# audio_perif.net
KiCad netlist of a schematic drawn in Altium Designer
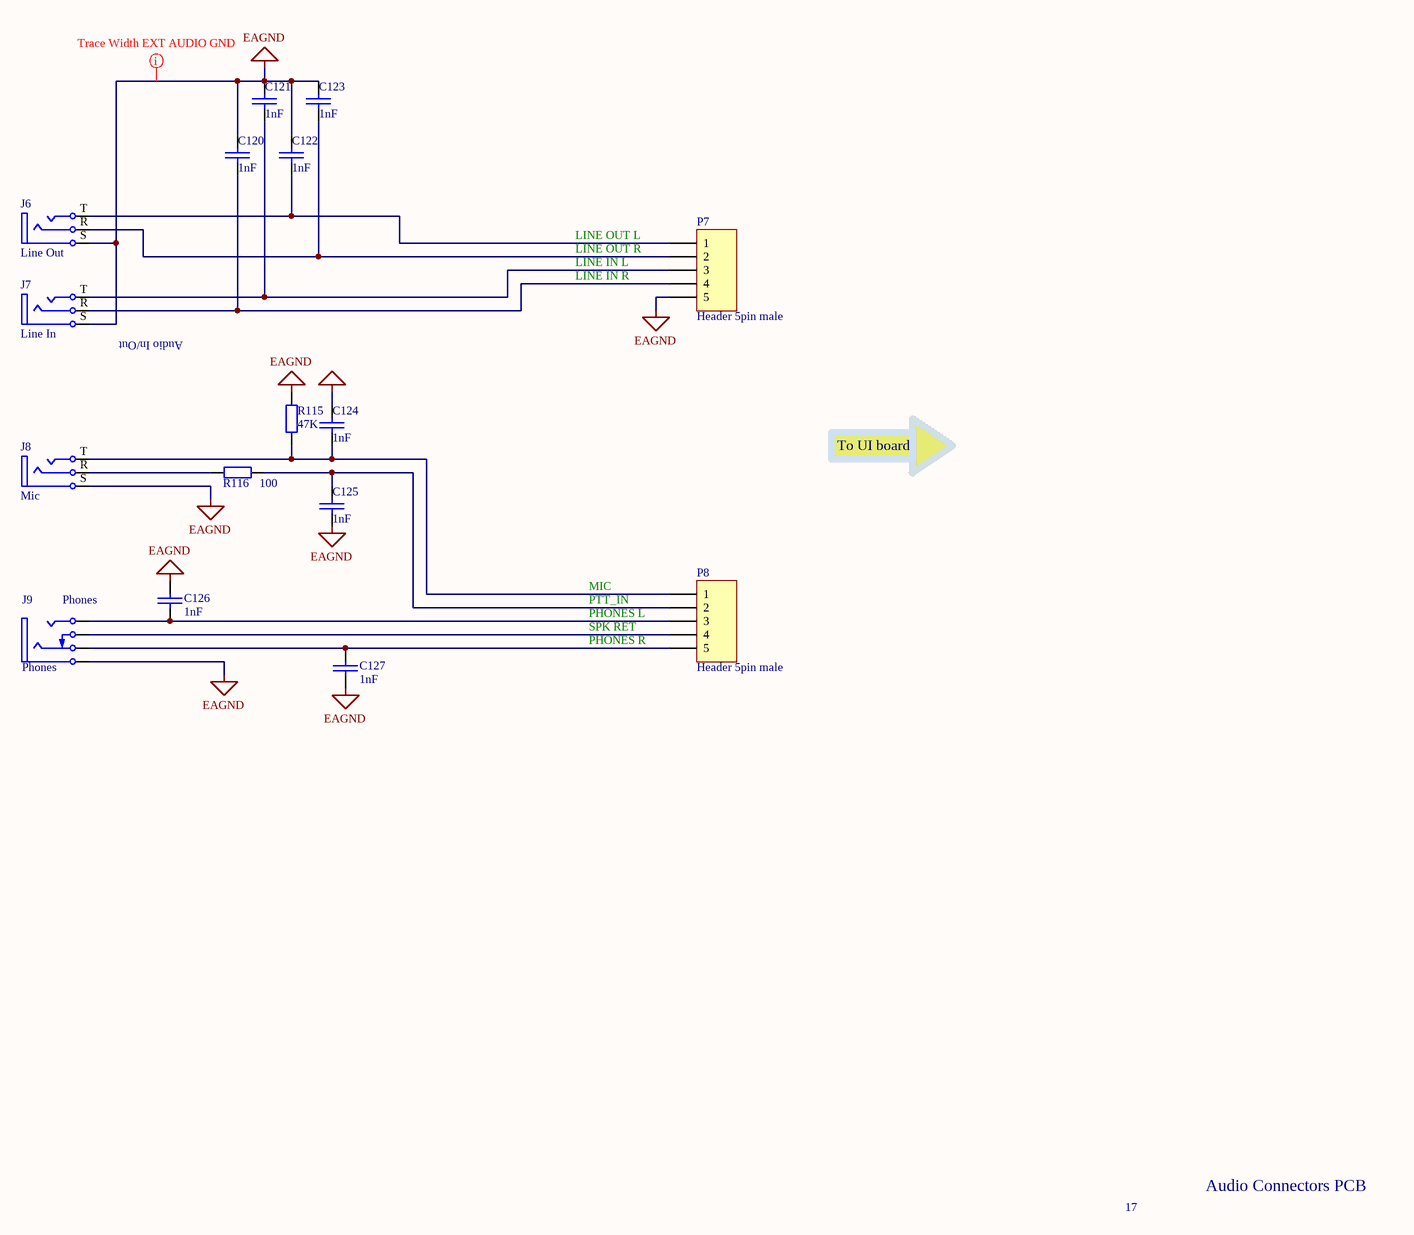
[diagram p0: audio_perif.SchDoc]

(export (version "E")
  (design (tool "Eeschema 10.0.6"))
  (components
    (comp (ref "C120")
      (value "1nF")
      (footprint "0805")
      (description "Capacitor")
      (libsource (lib "mcHF_ui") (part "CAP"))
    )
    (comp (ref "C121")
      (value "1nF")
      (footprint "0805")
      (description "Capacitor")
      (libsource (lib "mcHF_ui") (part "CAP"))
    )
    (comp (ref "C122")
      (value "1nF")
      (footprint "0805")
      (description "Capacitor")
      (libsource (lib "mcHF_ui") (part "CAP"))
    )
    (comp (ref "C123")
      (value "1nF")
      (footprint "0805")
      (description "Capacitor")
      (libsource (lib "mcHF_ui") (part "CAP"))
    )
    (comp (ref "C124")
      (value "1nF")
      (footprint "0805")
      (description "Capacitor")
      (libsource (lib "mcHF_ui") (part "CAP"))
    )
    (comp (ref "C125")
      (value "1nF")
      (footprint "0805")
      (description "Capacitor")
      (libsource (lib "mcHF_ui") (part "CAP"))
    )
    (comp (ref "C126")
      (value "1nF")
      (footprint "0805")
      (description "Capacitor")
      (libsource (lib "mcHF_ui") (part "CAP"))
    )
    (comp (ref "C127")
      (value "1nF")
      (footprint "0805")
      (description "Capacitor")
      (libsource (lib "mcHF_ui") (part "CAP"))
    )
    (comp (ref "J6")
      (value "Line Out")
      (footprint "MX-387GL_new1")
      (description "Jack Socket,Thru-Hole")
      (libsource (lib "mcHF_ui") (part "MX-387GL"))
    )
    (comp (ref "J7")
      (value "Line In")
      (footprint "MX-387GL_new1")
      (description "Jack Socket,Thru-Hole")
      (libsource (lib "mcHF_ui") (part "MX-387GL"))
    )
    (comp (ref "J8")
      (value "Mic")
      (footprint "MX-387GL_new1")
      (description "Jack Socket,Thru-Hole")
      (libsource (lib "mcHF_ui") (part "MX-387GL"))
    )
    (comp (ref "J9")
      (value "Phones")
      (footprint "KLBR4")
      (description "Jack Socket 4 pin")
      (fields (field (name "FUNCTION") "Phones"))
      (libsource (lib "mcHF_ui") (part "PhoneJack"))
    )
    (comp (ref "P7")
      (value "Header 5pin male")
      (footprint "HDR1X5")
      (description "Header, 5-Pin")
      (libsource (lib "__ui") (part "Header 5"))
    )
    (comp (ref "P8")
      (value "Header 5pin male")
      (footprint "HDR1X5")
      (description "Header, 5-Pin")
      (libsource (lib "__ui") (part "Header 5"))
    )
    (comp (ref "R115")
      (value "47K")
      (footprint "0805")
      (description "Resistor")
      (libsource (lib "mcHF_ui") (part "RES"))
    )
    (comp (ref "R116")
      (value "100")
      (footprint "0805")
      (description "Resistor")
      (libsource (lib "") (part "RES_1"))
    )
  )
  (nets
    (net (code "1") (name "EAGND") (class "Default")
      (node (ref "C120") (pin "1") (pinfunction "1_1") (pintype "passive"))
      (node (ref "C121") (pin "1") (pinfunction "1_1") (pintype "passive"))
      (node (ref "C122") (pin "1") (pinfunction "1_1") (pintype "passive"))
      (node (ref "C123") (pin "1") (pinfunction "1_1") (pintype "passive"))
      (node (ref "C124") (pin "1") (pinfunction "1_1") (pintype "passive"))
      (node (ref "C125") (pin "2") (pinfunction "2_2") (pintype "passive"))
      (node (ref "C126") (pin "2") (pinfunction "2_2") (pintype "passive"))
      (node (ref "C127") (pin "1") (pinfunction "1_1") (pintype "passive"))
      (node (ref "J6") (pin "S") (pinfunction "2_S") (pintype "power_in"))
      (node (ref "J7") (pin "S") (pinfunction "2_S") (pintype "power_in"))
      (node (ref "J8") (pin "S") (pinfunction "2_S") (pintype "power_in"))
      (node (ref "J9") (pin "S") (pinfunction "S_S") (pintype "power_in"))
      (node (ref "P7") (pin "5") (pinfunction "5_5") (pintype "passive"))
      (node (ref "R115") (pin "2") (pinfunction "2_2") (pintype "passive"))
    )
    (net (code "2") (name "Net-(C125-Pad1)") (class "Default")
      (node (ref "C125") (pin "1") (pinfunction "1_1") (pintype "passive"))
      (node (ref "P8") (pin "2") (pinfunction "2_2") (pintype "passive"))
      (node (ref "R116") (pin "2") (pinfunction "2_2") (pintype "passive"))
    )
    (net (code "3") (name "Net-(C126-Pad1)") (class "Default")
      (node (ref "C126") (pin "1") (pinfunction "1_1") (pintype "passive"))
      (node (ref "J9") (pin "T") (pinfunction "T_T") (pintype "passive"))
      (node (ref "P8") (pin "3") (pinfunction "3_3") (pintype "passive"))
    )
    (net (code "4") (name "Net-(C127-Pad2)") (class "Default")
      (node (ref "C127") (pin "2") (pinfunction "2_2") (pintype "passive"))
      (node (ref "J9") (pin "R") (pinfunction "R_R") (pintype "passive"))
      (node (ref "P8") (pin "5") (pinfunction "5_5") (pintype "passive"))
    )
    (net (code "5") (name "Net-(J6-1)") (class "Default")
      (node (ref "C122") (pin "2") (pinfunction "2_2") (pintype "passive"))
      (node (ref "J6") (pin "T") (pinfunction "1_T") (pintype "passive"))
      (node (ref "P7") (pin "1") (pinfunction "1_1") (pintype "passive"))
    )
    (net (code "6") (name "Net-(J6-3)") (class "Default")
      (node (ref "C123") (pin "2") (pinfunction "2_2") (pintype "passive"))
      (node (ref "J6") (pin "R") (pinfunction "3_R") (pintype "passive"))
      (node (ref "P7") (pin "2") (pinfunction "2_2") (pintype "passive"))
    )
    (net (code "7") (name "Net-(J7-1)") (class "Default")
      (node (ref "C121") (pin "2") (pinfunction "2_2") (pintype "passive"))
      (node (ref "J7") (pin "T") (pinfunction "1_T") (pintype "passive"))
      (node (ref "P7") (pin "3") (pinfunction "3_3") (pintype "passive"))
    )
    (net (code "8") (name "Net-(J7-3)") (class "Default")
      (node (ref "C120") (pin "2") (pinfunction "2_2") (pintype "passive"))
      (node (ref "J7") (pin "R") (pinfunction "3_R") (pintype "passive"))
      (node (ref "P7") (pin "4") (pinfunction "4_4") (pintype "passive"))
    )
    (net (code "9") (name "Net-(J8-1)") (class "Default")
      (node (ref "C124") (pin "2") (pinfunction "2_2") (pintype "passive"))
      (node (ref "J8") (pin "T") (pinfunction "1_T") (pintype "passive"))
      (node (ref "P8") (pin "1") (pinfunction "1_1") (pintype "passive"))
      (node (ref "R115") (pin "1") (pinfunction "1_1") (pintype "passive"))
    )
    (net (code "10") (name "Net-(J8-3)") (class "Default")
      (node (ref "J8") (pin "R") (pinfunction "3_R") (pintype "passive"))
      (node (ref "R116") (pin "1") (pinfunction "1_1") (pintype "passive"))
    )
    (net (code "11") (name "Net-(J9-PadB)") (class "Default")
      (node (ref "J9") (pin "B") (pinfunction "B_B") (pintype "passive"))
      (node (ref "P8") (pin "4") (pinfunction "4_4") (pintype "passive"))
    )
  )
)
